# esquema_sensor.net
KiCad netlist of a schematic drawn in EAGLE
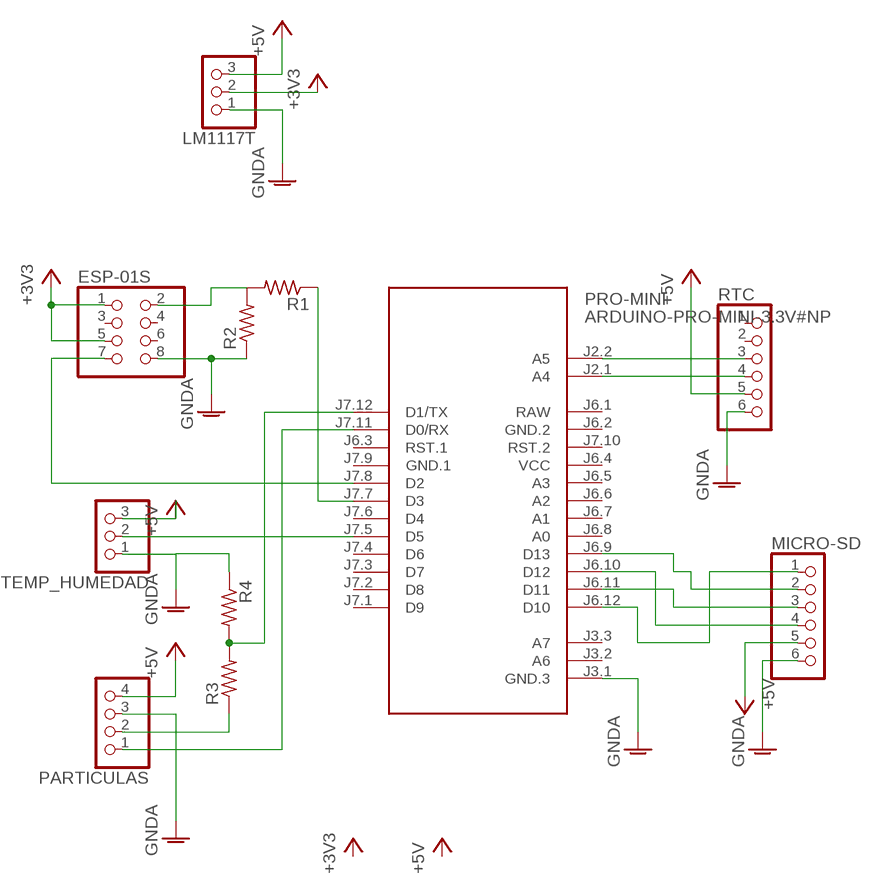
[diagram p0: schematic, sheet 1]

(export (version "E")
  (design (tool "Eeschema 10.0.6"))
  (components
    (comp (ref "ESP-01S")
      (value "PINHD-2X4")
      (footprint "eagle-import:2X04")
      (libsource (lib "eagle-import") (part "PINHD-2X4"))
    )
    (comp (ref "LM1117T")
      (value "PINHD-1X3")
      (footprint "eagle-import:1X03")
      (libsource (lib "eagle-import") (part "PINHD-1X3"))
    )
    (comp (ref "MICRO-SD")
      (value "PINHD-1X6B")
      (footprint "eagle-import:1X06-BIG")
      (libsource (lib "eagle-import") (part "PINHD-1X6B"))
    )
    (comp (ref "PARTICULAS")
      (value "PINHD-1X4")
      (footprint "eagle-import:1X04")
      (libsource (lib "eagle-import") (part "PINHD-1X4"))
    )
    (comp (ref "PRO-MINI")
      (value "ARDUINO-PRO-MINI-3.3V#NP")
      (footprint "eagle-import:ARDUINO-PRO-MINI#NP")
      (libsource (lib "eagle-import") (part "ARDUINO-PRO-MINI-#NP3.3V"))
    )
    (comp (ref "R1")
      (value "R-US_0207/7")
      (footprint "eagle-import:0207_7")
      (libsource (lib "eagle-import") (part "R-US_0207/7"))
    )
    (comp (ref "R2")
      (value "R-US_0207/7")
      (footprint "eagle-import:0207_7")
      (libsource (lib "eagle-import") (part "R-US_0207/7"))
    )
    (comp (ref "R3")
      (value "R-US_0207/7")
      (footprint "eagle-import:0207_7")
      (libsource (lib "eagle-import") (part "R-US_0207/7"))
    )
    (comp (ref "R4")
      (value "R-US_0207/7")
      (footprint "eagle-import:0207_7")
      (libsource (lib "eagle-import") (part "R-US_0207/7"))
    )
    (comp (ref "RTC")
      (value "PINHD-1X6B")
      (footprint "eagle-import:1X06-BIG")
      (libsource (lib "eagle-import") (part "PINHD-1X6B"))
    )
    (comp (ref "TEMP_HUMEDAD")
      (value "PINHD-1X3")
      (footprint "eagle-import:1X03")
      (libsource (lib "eagle-import") (part "PINHD-1X3"))
    )
  )
  (nets
    (net (code "1") (name "+3V3") (class "Default")
      (node (ref "ESP-01S") (pin "1") (pinfunction "1_1") (pintype "passive"))
      (node (ref "ESP-01S") (pin "5") (pinfunction "5_5") (pintype "passive"))
      (node (ref "LM1117T") (pin "2") (pinfunction "2_2") (pintype "passive"))
    )
    (net (code "2") (name "+5V") (class "Default")
      (node (ref "LM1117T") (pin "3") (pinfunction "3_3") (pintype "passive"))
      (node (ref "MICRO-SD") (pin "5") (pinfunction "5_5") (pintype "passive"))
      (node (ref "PARTICULAS") (pin "4") (pinfunction "4_4") (pintype "passive"))
      (node (ref "RTC") (pin "5") (pinfunction "5_5") (pintype "passive"))
      (node (ref "TEMP_HUMEDAD") (pin "3") (pinfunction "3_3") (pintype "passive"))
    )
    (net (code "3") (name "/GND.1") (class "Default")
      (node (ref "PRO-MINI") (pin "J7.9") (pinfunction "GND.1_J7.9") (pintype "power_in"))
    )
    (net (code "4") (name "/GND.2") (class "Default")
      (node (ref "PRO-MINI") (pin "J6.2") (pinfunction "GND.2_J6.2") (pintype "power_in"))
    )
    (net (code "5") (name "/RAW") (class "Default")
      (node (ref "PRO-MINI") (pin "J6.1") (pinfunction "RAW_J6.1") (pintype "power_in"))
    )
    (net (code "6") (name "/VCC") (class "Default")
      (node (ref "PRO-MINI") (pin "J6.4") (pinfunction "VCC_J6.4") (pintype "power_in"))
    )
    (net (code "7") (name "GNDA") (class "Default")
      (node (ref "ESP-01S") (pin "8") (pinfunction "8_8") (pintype "passive"))
      (node (ref "LM1117T") (pin "1") (pinfunction "1_1") (pintype "passive"))
      (node (ref "MICRO-SD") (pin "6") (pinfunction "6_6") (pintype "passive"))
      (node (ref "PARTICULAS") (pin "3") (pinfunction "3_3") (pintype "passive"))
      (node (ref "PRO-MINI") (pin "J3.1") (pinfunction "GND.3_J3.1") (pintype "bidirectional"))
      (node (ref "R2") (pin "1") (pinfunction "1_1") (pintype "passive"))
      (node (ref "R4") (pin "1") (pinfunction "1_1") (pintype "passive"))
      (node (ref "RTC") (pin "6") (pinfunction "6_6") (pintype "passive"))
      (node (ref "TEMP_HUMEDAD") (pin "1") (pinfunction "1_1") (pintype "passive"))
    )
    (net (code "8") (name "Net-(ESP-01S-Pad2)") (class "Default")
      (node (ref "ESP-01S") (pin "2") (pinfunction "2_2") (pintype "passive"))
      (node (ref "R1") (pin "2") (pinfunction "2_2") (pintype "passive"))
      (node (ref "R2") (pin "2") (pinfunction "2_2") (pintype "passive"))
    )
    (net (code "9") (name "Net-(PARTICULAS-Pad2)") (class "Default")
      (node (ref "PARTICULAS") (pin "2") (pinfunction "2_2") (pintype "passive"))
      (node (ref "R3") (pin "1") (pinfunction "1_1") (pintype "passive"))
    )
    (net (code "10") (name "Net-(PRO-MINI-A4)") (class "Default")
      (node (ref "PRO-MINI") (pin "J2.1") (pinfunction "A4_J2.1") (pintype "bidirectional"))
      (node (ref "RTC") (pin "4") (pinfunction "4_4") (pintype "passive"))
    )
    (net (code "11") (name "Net-(PRO-MINI-A5)") (class "Default")
      (node (ref "PRO-MINI") (pin "J2.2") (pinfunction "A5_J2.2") (pintype "bidirectional"))
      (node (ref "RTC") (pin "3") (pinfunction "3_3") (pintype "passive"))
    )
    (net (code "12") (name "Net-(PRO-MINI-D0{slash}RX)") (class "Default")
      (node (ref "PARTICULAS") (pin "1") (pinfunction "1_1") (pintype "passive"))
      (node (ref "PRO-MINI") (pin "J7.11") (pinfunction "D0/RX_J7.11") (pintype "bidirectional"))
    )
    (net (code "13") (name "Net-(PRO-MINI-D1{slash}TX)") (class "Default")
      (node (ref "PRO-MINI") (pin "J7.12") (pinfunction "D1/TX_J7.12") (pintype "bidirectional"))
      (node (ref "R3") (pin "2") (pinfunction "2_2") (pintype "passive"))
      (node (ref "R4") (pin "2") (pinfunction "2_2") (pintype "passive"))
    )
    (net (code "14") (name "Net-(PRO-MINI-D2)") (class "Default")
      (node (ref "ESP-01S") (pin "7") (pinfunction "7_7") (pintype "passive"))
      (node (ref "PRO-MINI") (pin "J7.8") (pinfunction "D2_J7.8") (pintype "bidirectional"))
    )
    (net (code "15") (name "Net-(PRO-MINI-D3)") (class "Default")
      (node (ref "PRO-MINI") (pin "J7.7") (pinfunction "D3_J7.7") (pintype "bidirectional"))
      (node (ref "R1") (pin "1") (pinfunction "1_1") (pintype "passive"))
    )
    (net (code "16") (name "Net-(PRO-MINI-D5)") (class "Default")
      (node (ref "PRO-MINI") (pin "J7.5") (pinfunction "D5_J7.5") (pintype "bidirectional"))
      (node (ref "TEMP_HUMEDAD") (pin "2") (pinfunction "2_2") (pintype "passive"))
    )
    (net (code "17") (name "Net-(PRO-MINI-D10)") (class "Default")
      (node (ref "MICRO-SD") (pin "1") (pinfunction "1_1") (pintype "passive"))
      (node (ref "PRO-MINI") (pin "J6.12") (pinfunction "D10_J6.12") (pintype "bidirectional"))
    )
    (net (code "18") (name "Net-(PRO-MINI-D11)") (class "Default")
      (node (ref "MICRO-SD") (pin "3") (pinfunction "3_3") (pintype "passive"))
      (node (ref "PRO-MINI") (pin "J6.11") (pinfunction "D11_J6.11") (pintype "bidirectional"))
    )
    (net (code "19") (name "Net-(PRO-MINI-D12)") (class "Default")
      (node (ref "MICRO-SD") (pin "4") (pinfunction "4_4") (pintype "passive"))
      (node (ref "PRO-MINI") (pin "J6.10") (pinfunction "D12_J6.10") (pintype "bidirectional"))
    )
    (net (code "20") (name "Net-(PRO-MINI-D13)") (class "Default")
      (node (ref "MICRO-SD") (pin "2") (pinfunction "2_2") (pintype "passive"))
      (node (ref "PRO-MINI") (pin "J6.9") (pinfunction "D13_J6.9") (pintype "bidirectional"))
    )
    (net (code "21") (name "unconnected-(ESP-01S-Pad3)") (class "Default")
      (node (ref "ESP-01S") (pin "3") (pinfunction "3_3") (pintype "passive"))
    )
    (net (code "22") (name "unconnected-(ESP-01S-Pad4)") (class "Default")
      (node (ref "ESP-01S") (pin "4") (pinfunction "4_4") (pintype "passive"))
    )
    (net (code "23") (name "unconnected-(ESP-01S-Pad6)") (class "Default")
      (node (ref "ESP-01S") (pin "6") (pinfunction "6_6") (pintype "passive"))
    )
    (net (code "24") (name "unconnected-(PRO-MINI-A0-PadJ6.8)") (class "Default")
      (node (ref "PRO-MINI") (pin "J6.8") (pinfunction "A0_J6.8") (pintype "bidirectional"))
    )
    (net (code "25") (name "unconnected-(PRO-MINI-A1-PadJ6.7)") (class "Default")
      (node (ref "PRO-MINI") (pin "J6.7") (pinfunction "A1_J6.7") (pintype "bidirectional"))
    )
    (net (code "26") (name "unconnected-(PRO-MINI-A2-PadJ6.6)") (class "Default")
      (node (ref "PRO-MINI") (pin "J6.6") (pinfunction "A2_J6.6") (pintype "bidirectional"))
    )
    (net (code "27") (name "unconnected-(PRO-MINI-A3-PadJ6.5)") (class "Default")
      (node (ref "PRO-MINI") (pin "J6.5") (pinfunction "A3_J6.5") (pintype "bidirectional"))
    )
    (net (code "28") (name "unconnected-(PRO-MINI-A6-PadJ3.2)") (class "Default")
      (node (ref "PRO-MINI") (pin "J3.2") (pinfunction "A6_J3.2") (pintype "bidirectional"))
    )
    (net (code "29") (name "unconnected-(PRO-MINI-A7-PadJ3.3)") (class "Default")
      (node (ref "PRO-MINI") (pin "J3.3") (pinfunction "A7_J3.3") (pintype "bidirectional"))
    )
    (net (code "30") (name "unconnected-(PRO-MINI-D4-PadJ7.6)") (class "Default")
      (node (ref "PRO-MINI") (pin "J7.6") (pinfunction "D4_J7.6") (pintype "bidirectional"))
    )
    (net (code "31") (name "unconnected-(PRO-MINI-D6-PadJ7.4)") (class "Default")
      (node (ref "PRO-MINI") (pin "J7.4") (pinfunction "D6_J7.4") (pintype "bidirectional"))
    )
    (net (code "32") (name "unconnected-(PRO-MINI-D7-PadJ7.3)") (class "Default")
      (node (ref "PRO-MINI") (pin "J7.3") (pinfunction "D7_J7.3") (pintype "bidirectional"))
    )
    (net (code "33") (name "unconnected-(PRO-MINI-D8-PadJ7.2)") (class "Default")
      (node (ref "PRO-MINI") (pin "J7.2") (pinfunction "D8_J7.2") (pintype "bidirectional"))
    )
    (net (code "34") (name "unconnected-(PRO-MINI-D9-PadJ7.1)") (class "Default")
      (node (ref "PRO-MINI") (pin "J7.1") (pinfunction "D9_J7.1") (pintype "bidirectional"))
    )
    (net (code "35") (name "unconnected-(PRO-MINI-RST.1-PadJ6.3)") (class "Default")
      (node (ref "PRO-MINI") (pin "J6.3") (pinfunction "RST.1_J6.3") (pintype "bidirectional"))
    )
    (net (code "36") (name "unconnected-(PRO-MINI-RST.2-PadJ7.10)") (class "Default")
      (node (ref "PRO-MINI") (pin "J7.10") (pinfunction "RST.2_J7.10") (pintype "bidirectional"))
    )
    (net (code "37") (name "unconnected-(RTC-Pad1)") (class "Default")
      (node (ref "RTC") (pin "1") (pinfunction "1_1") (pintype "passive"))
    )
    (net (code "38") (name "unconnected-(RTC-Pad2)") (class "Default")
      (node (ref "RTC") (pin "2") (pinfunction "2_2") (pintype "passive"))
    )
  )
)
